# Medium_switch.net
KiCad netlist of a schematic drawn in EAGLE
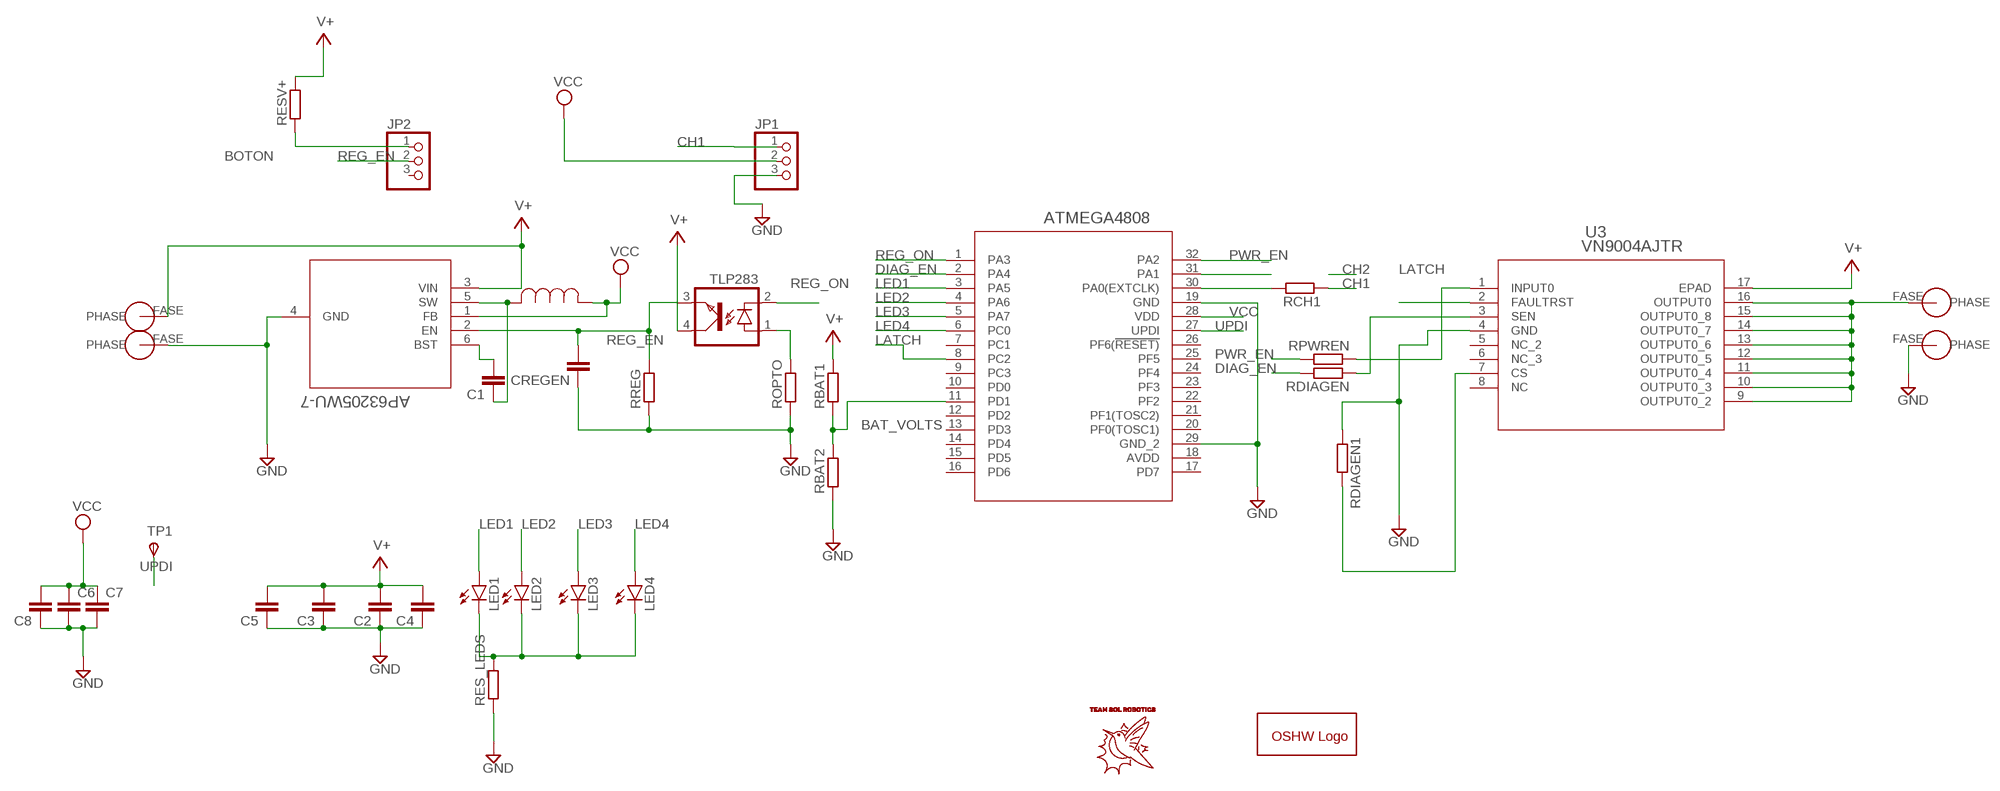
[diagram p0: schematic, sheet 1]

(export (version "E")
  (design (tool "Eeschema 10.0.6"))
  (components
    (comp (ref "BAT+")
      (value "PHASE")
      (footprint "eagle-import:POWEROUT")
      (libsource (lib "eagle-import") (part "PHASE"))
    )
    (comp (ref "C1")
      (value "C-EUC0402")
      (footprint "eagle-import:C0402")
      (libsource (lib "eagle-import") (part "C-EUC0402"))
    )
    (comp (ref "C2")
      (value "C-EUC1206")
      (footprint "eagle-import:C1206")
      (libsource (lib "eagle-import") (part "C-EUC1206"))
    )
    (comp (ref "C3")
      (value "C-EUC0402")
      (footprint "eagle-import:C0402")
      (libsource (lib "eagle-import") (part "C-EUC0402"))
    )
    (comp (ref "C4")
      (value "C-EUC1206")
      (footprint "eagle-import:C1206")
      (libsource (lib "eagle-import") (part "C-EUC1206"))
    )
    (comp (ref "C5")
      (value "C-EUC0603")
      (footprint "eagle-import:C0603")
      (libsource (lib "eagle-import") (part "C-EUC0603"))
    )
    (comp (ref "C6")
      (value "C-EUC0805")
      (footprint "eagle-import:C0805")
      (libsource (lib "eagle-import") (part "C-EUC0805"))
    )
    (comp (ref "C7")
      (value "C-EUC0805")
      (footprint "eagle-import:C0805")
      (libsource (lib "eagle-import") (part "C-EUC0805"))
    )
    (comp (ref "C8")
      (value "C-EUC0402")
      (footprint "eagle-import:C0402")
      (libsource (lib "eagle-import") (part "C-EUC0402"))
    )
    (comp (ref "CREGEN")
      (value "C-EUC0402")
      (footprint "eagle-import:C0402")
      (libsource (lib "eagle-import") (part "C-EUC0402"))
    )
    (comp (ref "FASEA1")
      (value "PHASE")
      (footprint "eagle-import:POWEROUT")
      (libsource (lib "eagle-import") (part "PHASE"))
    )
    (comp (ref "FASEA3")
      (value "PHASE")
      (footprint "eagle-import:POWEROUT")
      (libsource (lib "eagle-import") (part "PHASE"))
    )
    (comp (ref "GOLD_ORB_SM1")
      (value "OSHWLOGOLOGO5MM")
      (footprint "eagle-import:OSHW_5MM")
      (libsource (lib "eagle-import") (part "OSHWLOGOLOGO5MM"))
    )
    (comp (ref "JP1")
      (value "PINHD-1X03_2.54-S")
      (footprint "eagle-import:1X03-S")
      (libsource (lib "eagle-import") (part "PINHD-1X03_2.54-S"))
    )
    (comp (ref "JP2")
      (value "PINHD-1X03_2.54-S")
      (footprint "eagle-import:1X03-S")
      (libsource (lib "eagle-import") (part "PINHD-1X03_2.54-S"))
    )
    (comp (ref "LED1")
      (value "LEDSML0603")
      (footprint "eagle-import:SML0603")
      (libsource (lib "eagle-import") (part "LEDSML0603"))
    )
    (comp (ref "LED2")
      (value "LEDSML0603")
      (footprint "eagle-import:SML0603")
      (libsource (lib "eagle-import") (part "LEDSML0603"))
    )
    (comp (ref "LED3")
      (value "LEDSML0603")
      (footprint "eagle-import:SML0603")
      (libsource (lib "eagle-import") (part "LEDSML0603"))
    )
    (comp (ref "LED4")
      (value "LEDSML0603")
      (footprint "eagle-import:SML0603")
      (libsource (lib "eagle-import") (part "LEDSML0603"))
    )
    (comp (ref "OK1")
      (value "TLP283")
      (footprint "eagle-import:MINI-FLAT-4")
      (libsource (lib "eagle-import") (part "TLP283"))
    )
    (comp (ref "OUTPUTPWR")
      (value "PHASE")
      (footprint "eagle-import:POWEROUT")
      (libsource (lib "eagle-import") (part "PHASE"))
    )
    (comp (ref "RBAT1")
      (value "R-EU_R0603")
      (footprint "eagle-import:R0603")
      (libsource (lib "eagle-import") (part "R-EU_R0603"))
    )
    (comp (ref "RBAT2")
      (value "R-EU_R0603")
      (footprint "eagle-import:R0603")
      (libsource (lib "eagle-import") (part "R-EU_R0603"))
    )
    (comp (ref "RCH1")
      (value "R-EU_R0603")
      (footprint "eagle-import:R0603")
      (libsource (lib "eagle-import") (part "R-EU_R0603"))
    )
    (comp (ref "RDIAGEN")
      (value "R-EU_R0603")
      (footprint "eagle-import:R0603")
      (libsource (lib "eagle-import") (part "R-EU_R0603"))
    )
    (comp (ref "RDIAGEN1")
      (value "R-EU_R0603")
      (footprint "eagle-import:R0603")
      (libsource (lib "eagle-import") (part "R-EU_R0603"))
    )
    (comp (ref "RESV+")
      (value "R-EU_R0603")
      (footprint "eagle-import:R0603")
      (libsource (lib "eagle-import") (part "R-EU_R0603"))
    )
    (comp (ref "RES_LEDS")
      (value "R-EU_R0603")
      (footprint "eagle-import:R0603")
      (libsource (lib "eagle-import") (part "R-EU_R0603"))
    )
    (comp (ref "ROPTO")
      (value "R-EU_R0603")
      (footprint "eagle-import:R0603")
      (libsource (lib "eagle-import") (part "R-EU_R0603"))
    )
    (comp (ref "RPWREN")
      (value "R-EU_R0603")
      (footprint "eagle-import:R0603")
      (libsource (lib "eagle-import") (part "R-EU_R0603"))
    )
    (comp (ref "RREG")
      (value "R-EU_R0603")
      (footprint "eagle-import:R0603")
      (libsource (lib "eagle-import") (part "R-EU_R0603"))
    )
    (comp (ref "TP1")
      (value "TPSTP10SQ")
      (footprint "eagle-import:TP10SQ")
      (libsource (lib "eagle-import") (part "TPSTP10SQ"))
    )
    (comp (ref "U$1")
      (value "ATMEGA4808")
      (footprint "eagle-import:QFP80P900X900X120-32N")
      (libsource (lib "eagle-import") (part "ATMEGA4808"))
    )
    (comp (ref "U$3")
      (value "INDUCTOR4.7")
      (footprint "eagle-import:IND_NRS5030T100MMGJ_TAY")
      (libsource (lib "eagle-import") (part "INDUCTOR4.7"))
    )
    (comp (ref "U2")
      (value "AP63205WU-7")
      (footprint "eagle-import:SOIC_05WU-7_DIO")
      (fields (field (name "COPYRIGHT") "Copyright (C) 2018 Accelerated Designs. All rights reserved"))
      (libsource (lib "eagle-import") (part "AP63205WU-7"))
    )
    (comp (ref "U3")
      (value "VN9004AJTR")
      (footprint "eagle-import:POWERSSO16_VN9004_STM")
      (fields (field (name "COPYRIGHT") "Copyright (C) 2023 Ultra Librarian. All rights reserved."))
      (libsource (lib "eagle-import") (part "VN9004AJTR"))
    )
  )
  (nets
    (net (code "1") (name "/AVDD") (class "Default")
      (node (ref "U$1") (pin "18") (pinfunction "AVDD_18") (pintype "power_in"))
    )
    (net (code "2") (name "/BAT_VOLTS") (class "Default")
      (node (ref "RBAT1") (pin "1") (pinfunction "1_1") (pintype "passive"))
      (node (ref "RBAT2") (pin "2") (pinfunction "2_2") (pintype "passive"))
      (node (ref "U$1") (pin "11") (pinfunction "PD1_11") (pintype "bidirectional"))
    )
    (net (code "3") (name "/BOTON") (class "Default")
      (node (ref "JP2") (pin "1") (pinfunction "1_1") (pintype "passive"))
      (node (ref "RESV+") (pin "1") (pinfunction "1_1") (pintype "passive"))
    )
    (net (code "4") (name "/CH1") (class "Default")
      (node (ref "JP1") (pin "1") (pinfunction "1_1") (pintype "passive"))
      (node (ref "RCH1") (pin "1") (pinfunction "1_1") (pintype "passive"))
    )
    (net (code "6") (name "/DIAG_EN") (class "Default")
      (node (ref "RDIAGEN") (pin "2") (pinfunction "2_2") (pintype "passive"))
      (node (ref "U$1") (pin "2") (pinfunction "PA4_2") (pintype "bidirectional"))
    )
    (net (code "7") (name "/LATCH") (class "Default")
      (node (ref "U$1") (pin "8") (pinfunction "PC2_8") (pintype "bidirectional"))
      (node (ref "U3") (pin "2") (pinfunction "FAULTRST_2") (pintype "output"))
    )
    (net (code "8") (name "/LED1") (class "Default")
      (node (ref "LED1") (pin "A") (pinfunction "A_A") (pintype "passive"))
      (node (ref "U$1") (pin "3") (pinfunction "PA5_3") (pintype "bidirectional"))
    )
    (net (code "9") (name "/LED2") (class "Default")
      (node (ref "LED2") (pin "A") (pinfunction "A_A") (pintype "passive"))
      (node (ref "U$1") (pin "4") (pinfunction "PA6_4") (pintype "bidirectional"))
    )
    (net (code "10") (name "/LED3") (class "Default")
      (node (ref "LED3") (pin "A") (pinfunction "A_A") (pintype "passive"))
      (node (ref "U$1") (pin "5") (pinfunction "PA7_5") (pintype "bidirectional"))
    )
    (net (code "11") (name "/LED4") (class "Default")
      (node (ref "LED4") (pin "A") (pinfunction "A_A") (pintype "passive"))
      (node (ref "U$1") (pin "6") (pinfunction "PC0_6") (pintype "bidirectional"))
    )
    (net (code "12") (name "/PWR_EN") (class "Default")
      (node (ref "RPWREN") (pin "2") (pinfunction "2_2") (pintype "passive"))
      (node (ref "U$1") (pin "32") (pinfunction "PA2_32") (pintype "bidirectional"))
    )
    (net (code "13") (name "/REG_EN") (class "Default")
      (node (ref "CREGEN") (pin "2") (pinfunction "2_2") (pintype "passive"))
      (node (ref "JP2") (pin "2") (pinfunction "2_2") (pintype "passive"))
      (node (ref "OK1") (pin "3") (pinfunction "EMIT_3") (pintype "passive"))
      (node (ref "RREG") (pin "2") (pinfunction "2_2") (pintype "passive"))
      (node (ref "U2") (pin "2") (pinfunction "EN_2") (pintype "passive"))
    )
    (net (code "14") (name "/REG_ON") (class "Default")
      (node (ref "OK1") (pin "2") (pinfunction "C_2") (pintype "passive"))
      (node (ref "U$1") (pin "1") (pinfunction "PA3_1") (pintype "bidirectional"))
    )
    (net (code "15") (name "/UPDI") (class "Default")
      (node (ref "TP1") (pin "TP") (pinfunction "PP_TP") (pintype "input"))
      (node (ref "U$1") (pin "27") (pinfunction "UPDI_27") (pintype "bidirectional"))
    )
    (net (code "16") (name "GND") (class "Default")
      (node (ref "C2") (pin "1") (pinfunction "1_1") (pintype "passive"))
      (node (ref "C3") (pin "1") (pinfunction "1_1") (pintype "passive"))
      (node (ref "C4") (pin "1") (pinfunction "1_1") (pintype "passive"))
      (node (ref "C5") (pin "1") (pinfunction "1_1") (pintype "passive"))
      (node (ref "C6") (pin "2") (pinfunction "2_2") (pintype "passive"))
      (node (ref "C7") (pin "2") (pinfunction "2_2") (pintype "passive"))
      (node (ref "C8") (pin "1") (pinfunction "1_1") (pintype "passive"))
      (node (ref "CREGEN") (pin "1") (pinfunction "1_1") (pintype "passive"))
      (node (ref "FASEA1") (pin "FASE") (pinfunction "PHASE_FASE") (pintype "bidirectional"))
      (node (ref "FASEA3") (pin "FASE") (pinfunction "PHASE_FASE") (pintype "bidirectional"))
      (node (ref "JP1") (pin "3") (pinfunction "3_3") (pintype "passive"))
      (node (ref "RBAT2") (pin "1") (pinfunction "1_1") (pintype "passive"))
      (node (ref "RDIAGEN1") (pin "1") (pinfunction "1_1") (pintype "passive"))
      (node (ref "RES_LEDS") (pin "1") (pinfunction "1_1") (pintype "passive"))
      (node (ref "ROPTO") (pin "1") (pinfunction "1_1") (pintype "passive"))
      (node (ref "RREG") (pin "1") (pinfunction "1_1") (pintype "passive"))
      (node (ref "U$1") (pin "19") (pinfunction "GND_19") (pintype "passive"))
      (node (ref "U$1") (pin "29") (pinfunction "GND_2_29") (pintype "passive"))
      (node (ref "U2") (pin "4") (pinfunction "GND_4") (pintype "passive"))
      (node (ref "U3") (pin "4") (pinfunction "GND_4") (pintype "passive"))
    )
    (net (code "17") (name "Net-(LED1-PadC)") (class "Default")
      (node (ref "LED1") (pin "C") (pinfunction "C_C") (pintype "passive"))
      (node (ref "LED2") (pin "C") (pinfunction "C_C") (pintype "passive"))
      (node (ref "LED3") (pin "C") (pinfunction "C_C") (pintype "passive"))
      (node (ref "LED4") (pin "C") (pinfunction "C_C") (pintype "passive"))
      (node (ref "RES_LEDS") (pin "2") (pinfunction "2_2") (pintype "passive"))
    )
    (net (code "18") (name "Net-(OK1-A)") (class "Default")
      (node (ref "OK1") (pin "1") (pinfunction "A_1") (pintype "passive"))
      (node (ref "ROPTO") (pin "2") (pinfunction "2_2") (pintype "passive"))
    )
    (net (code "19") (name "Net-(OUTPUTPWR-PHASE)") (class "Default")
      (node (ref "OUTPUTPWR") (pin "FASE") (pinfunction "PHASE_FASE") (pintype "bidirectional"))
      (node (ref "U3") (pin "10") (pinfunction "OUTPUT0_3_10") (pintype "output"))
      (node (ref "U3") (pin "11") (pinfunction "OUTPUT0_4_11") (pintype "output"))
      (node (ref "U3") (pin "12") (pinfunction "OUTPUT0_5_12") (pintype "output"))
      (node (ref "U3") (pin "13") (pinfunction "OUTPUT0_6_13") (pintype "output"))
      (node (ref "U3") (pin "14") (pinfunction "OUTPUT0_7_14") (pintype "output"))
      (node (ref "U3") (pin "15") (pinfunction "OUTPUT0_8_15") (pintype "output"))
      (node (ref "U3") (pin "16") (pinfunction "OUTPUT0_16") (pintype "output"))
      (node (ref "U3") (pin "9") (pinfunction "OUTPUT0_2_9") (pintype "output"))
    )
    (net (code "20") (name "Net-(U$1-PA0(EXTCLK))") (class "Default")
      (node (ref "RCH1") (pin "2") (pinfunction "2_2") (pintype "passive"))
      (node (ref "U$1") (pin "30") (pinfunction "PA0(EXTCLK)_30") (pintype "bidirectional"))
    )
    (net (code "21") (name "Net-(U2-BST)") (class "Default")
      (node (ref "C1") (pin "2") (pinfunction "2_2") (pintype "passive"))
      (node (ref "U2") (pin "6") (pinfunction "BST_6") (pintype "passive"))
    )
    (net (code "22") (name "Net-(U2-SW)") (class "Default")
      (node (ref "C1") (pin "1") (pinfunction "1_1") (pintype "passive"))
      (node (ref "U$3") (pin "2") (pinfunction "2_2") (pintype "passive"))
      (node (ref "U2") (pin "5") (pinfunction "SW_5") (pintype "passive"))
    )
    (net (code "23") (name "Net-(U3-CS)") (class "Default")
      (node (ref "RDIAGEN1") (pin "2") (pinfunction "2_2") (pintype "passive"))
      (node (ref "U3") (pin "7") (pinfunction "CS_7") (pintype "output"))
    )
    (net (code "24") (name "Net-(U3-INPUT0)") (class "Default")
      (node (ref "RPWREN") (pin "1") (pinfunction "1_1") (pintype "passive"))
      (node (ref "U3") (pin "1") (pinfunction "INPUT0_1") (pintype "input"))
    )
    (net (code "25") (name "Net-(U3-SEN)") (class "Default")
      (node (ref "RDIAGEN") (pin "1") (pinfunction "1_1") (pintype "passive"))
      (node (ref "U3") (pin "3") (pinfunction "SEN_3") (pintype "output"))
    )
    (net (code "26") (name "V+") (class "Default")
      (node (ref "BAT+") (pin "FASE") (pinfunction "PHASE_FASE") (pintype "bidirectional"))
      (node (ref "C2") (pin "2") (pinfunction "2_2") (pintype "passive"))
      (node (ref "C3") (pin "2") (pinfunction "2_2") (pintype "passive"))
      (node (ref "C4") (pin "2") (pinfunction "2_2") (pintype "passive"))
      (node (ref "C5") (pin "2") (pinfunction "2_2") (pintype "passive"))
      (node (ref "OK1") (pin "4") (pinfunction "COL_4") (pintype "passive"))
      (node (ref "RBAT1") (pin "2") (pinfunction "2_2") (pintype "passive"))
      (node (ref "RESV+") (pin "2") (pinfunction "2_2") (pintype "passive"))
      (node (ref "U2") (pin "3") (pinfunction "VIN_3") (pintype "passive"))
      (node (ref "U3") (pin "17") (pinfunction "EPAD_17") (pintype "passive"))
    )
    (net (code "27") (name "VCC") (class "Default")
      (node (ref "C6") (pin "1") (pinfunction "1_1") (pintype "passive"))
      (node (ref "C7") (pin "1") (pinfunction "1_1") (pintype "passive"))
      (node (ref "C8") (pin "2") (pinfunction "2_2") (pintype "passive"))
      (node (ref "JP1") (pin "2") (pinfunction "2_2") (pintype "passive"))
      (node (ref "U$1") (pin "28") (pinfunction "VDD_28") (pintype "power_in"))
      (node (ref "U$3") (pin "1") (pinfunction "1_1") (pintype "passive"))
      (node (ref "U2") (pin "1") (pinfunction "FB_1") (pintype "passive"))
    )
    (net (code "28") (name "unconnected-(JP2-Pad3)") (class "Default")
      (node (ref "JP2") (pin "3") (pinfunction "3_3") (pintype "passive"))
    )
    (net (code "29") (name "unconnected-(U$1-PA1-Pad31)") (class "Default")
      (node (ref "U$1") (pin "31") (pinfunction "PA1_31") (pintype "bidirectional"))
    )
    (net (code "30") (name "unconnected-(U$1-PC1-Pad7)") (class "Default")
      (node (ref "U$1") (pin "7") (pinfunction "PC1_7") (pintype "bidirectional"))
    )
    (net (code "31") (name "unconnected-(U$1-PC3-Pad9)") (class "Default")
      (node (ref "U$1") (pin "9") (pinfunction "PC3_9") (pintype "bidirectional"))
    )
    (net (code "32") (name "unconnected-(U$1-PD0-Pad10)") (class "Default")
      (node (ref "U$1") (pin "10") (pinfunction "PD0_10") (pintype "bidirectional"))
    )
    (net (code "33") (name "unconnected-(U$1-PD2-Pad12)") (class "Default")
      (node (ref "U$1") (pin "12") (pinfunction "PD2_12") (pintype "bidirectional"))
    )
    (net (code "34") (name "unconnected-(U$1-PD3-Pad13)") (class "Default")
      (node (ref "U$1") (pin "13") (pinfunction "PD3_13") (pintype "bidirectional"))
    )
    (net (code "35") (name "unconnected-(U$1-PD4-Pad14)") (class "Default")
      (node (ref "U$1") (pin "14") (pinfunction "PD4_14") (pintype "bidirectional"))
    )
    (net (code "36") (name "unconnected-(U$1-PD5-Pad15)") (class "Default")
      (node (ref "U$1") (pin "15") (pinfunction "PD5_15") (pintype "bidirectional"))
    )
    (net (code "37") (name "unconnected-(U$1-PD6-Pad16)") (class "Default")
      (node (ref "U$1") (pin "16") (pinfunction "PD6_16") (pintype "bidirectional"))
    )
    (net (code "38") (name "unconnected-(U$1-PD7-Pad17)") (class "Default")
      (node (ref "U$1") (pin "17") (pinfunction "PD7_17") (pintype "bidirectional"))
    )
    (net (code "39") (name "unconnected-(U$1-PF0(TOSC1)-Pad20)") (class "Default")
      (node (ref "U$1") (pin "20") (pinfunction "PF0(TOSC1)_20") (pintype "bidirectional"))
    )
    (net (code "40") (name "unconnected-(U$1-PF1(TOSC2)-Pad21)") (class "Default")
      (node (ref "U$1") (pin "21") (pinfunction "PF1(TOSC2)_21") (pintype "bidirectional"))
    )
    (net (code "41") (name "unconnected-(U$1-PF2-Pad22)") (class "Default")
      (node (ref "U$1") (pin "22") (pinfunction "PF2_22") (pintype "bidirectional"))
    )
    (net (code "42") (name "unconnected-(U$1-PF3-Pad23)") (class "Default")
      (node (ref "U$1") (pin "23") (pinfunction "PF3_23") (pintype "bidirectional"))
    )
    (net (code "43") (name "unconnected-(U$1-PF4-Pad24)") (class "Default")
      (node (ref "U$1") (pin "24") (pinfunction "PF4_24") (pintype "bidirectional"))
    )
    (net (code "44") (name "unconnected-(U$1-PF5-Pad25)") (class "Default")
      (node (ref "U$1") (pin "25") (pinfunction "PF5_25") (pintype "bidirectional"))
    )
    (net (code "45") (name "unconnected-(U$1-PF6(~{RESET})-Pad26)") (class "Default")
      (node (ref "U$1") (pin "26") (pinfunction "PF6(~{RESET})_26") (pintype "bidirectional"))
    )
    (net (code "46") (name "unconnected-(U3-NC-Pad8)") (class "Default")
      (node (ref "U3") (pin "8") (pinfunction "NC_8") (pintype "no_connect"))
    )
    (net (code "47") (name "unconnected-(U3-NC_2-Pad5)") (class "Default")
      (node (ref "U3") (pin "5") (pinfunction "NC_2_5") (pintype "no_connect"))
    )
    (net (code "48") (name "unconnected-(U3-NC_3-Pad6)") (class "Default")
      (node (ref "U3") (pin "6") (pinfunction "NC_3_6") (pintype "no_connect"))
    )
  )
)
